# BPMLabLineRX.net
KiCad netlist of a schematic drawn in EAGLE
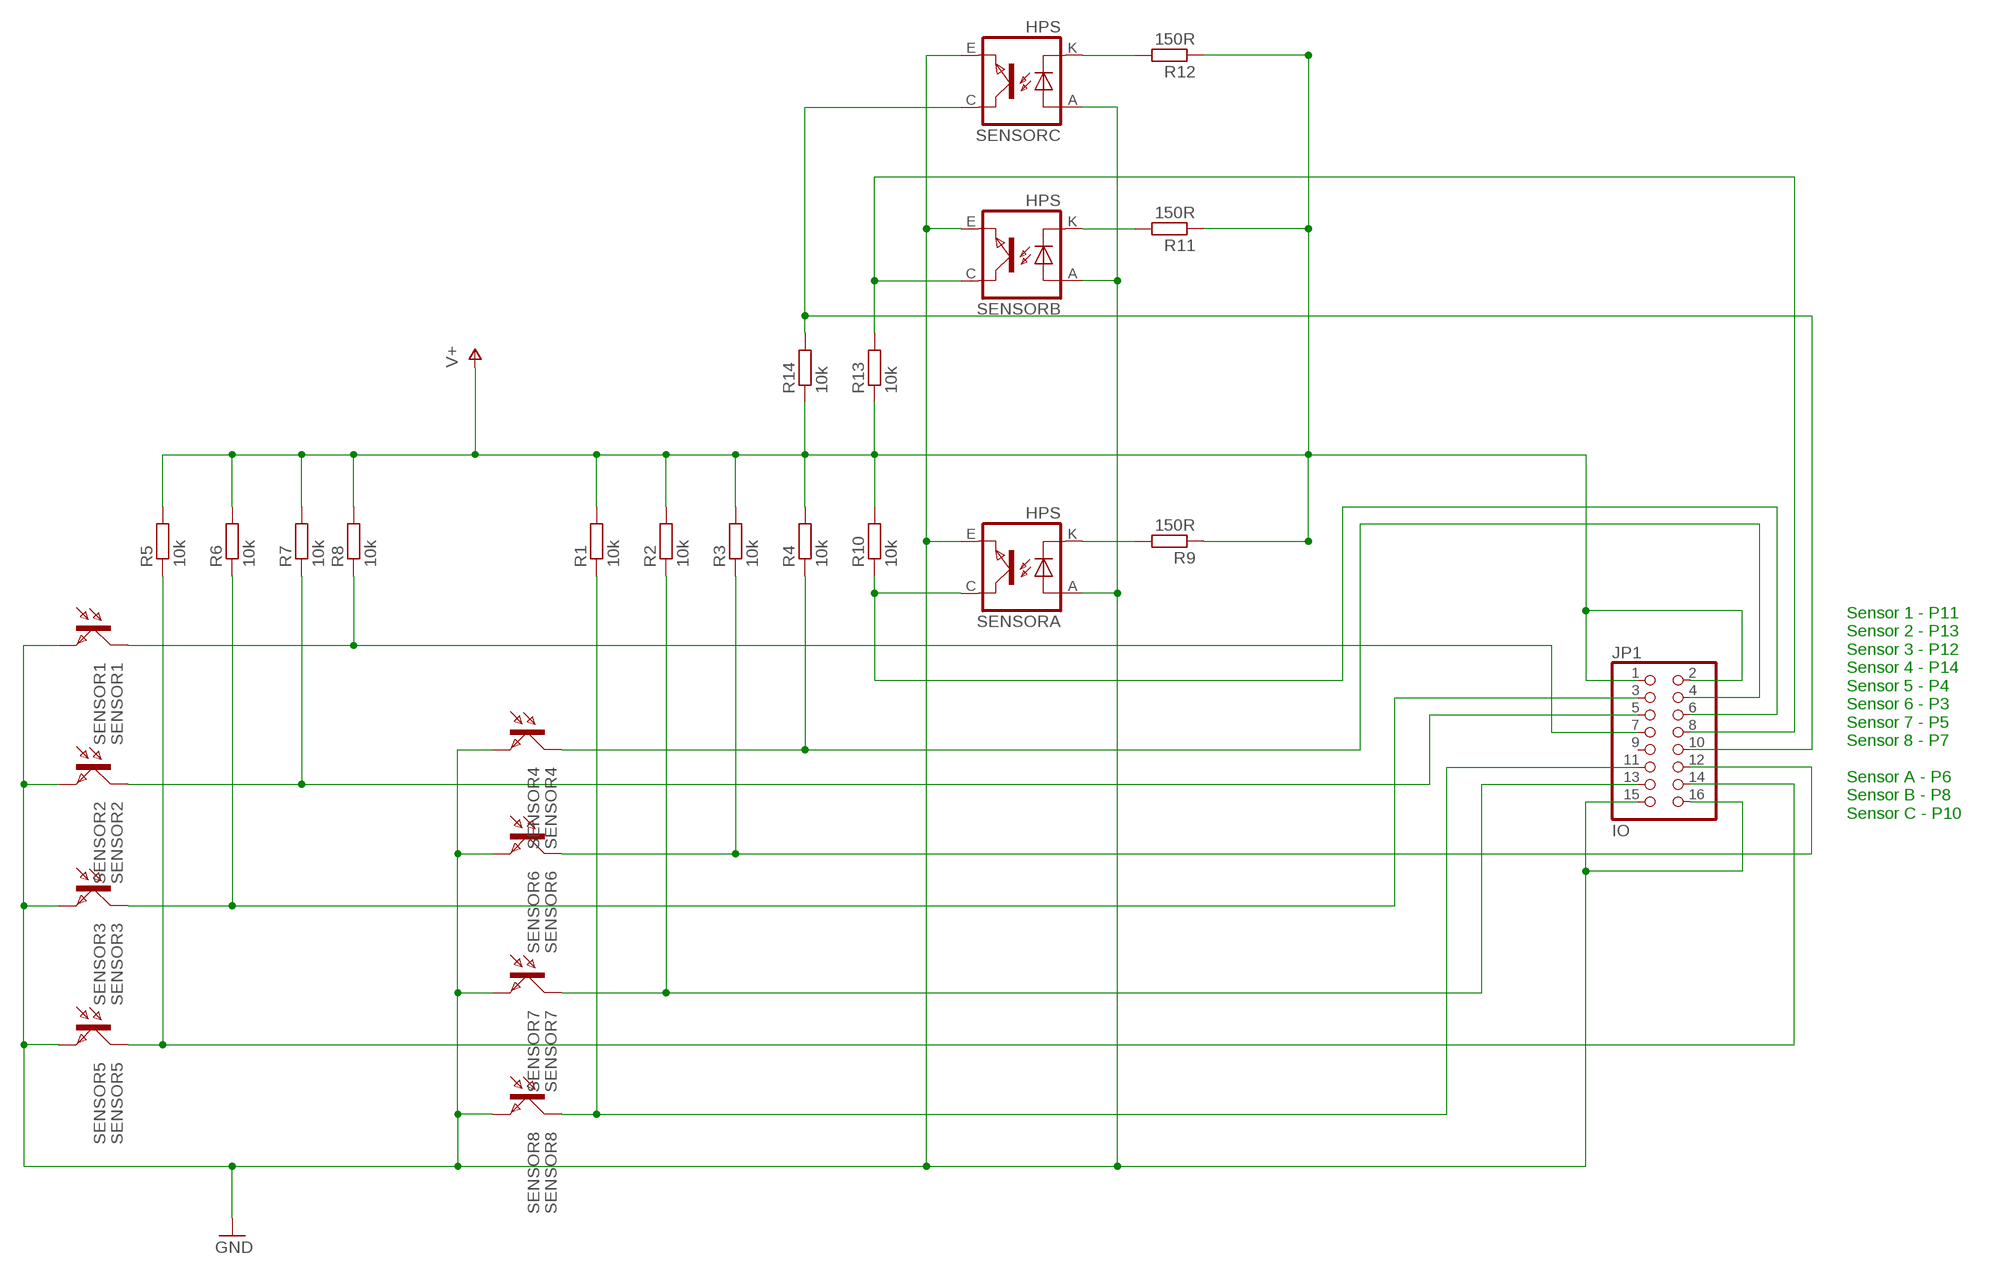
[diagram p0: schematic, sheet 1]

(export (version "E")
  (design (tool "Eeschema 10.0.6"))
  (components
    (comp (ref "JP1")
      (value "IO")
      (footprint "eagle-import:2X08")
      (libsource (lib "eagle-import") (part "PINHD-2X8"))
    )
    (comp (ref "R1")
      (value "10k")
      (footprint "eagle-import:M0805")
      (libsource (lib "eagle-import") (part "R-EU_M0805"))
    )
    (comp (ref "R2")
      (value "10k")
      (footprint "eagle-import:M0805")
      (libsource (lib "eagle-import") (part "R-EU_M0805"))
    )
    (comp (ref "R3")
      (value "10k")
      (footprint "eagle-import:M0805")
      (libsource (lib "eagle-import") (part "R-EU_M0805"))
    )
    (comp (ref "R4")
      (value "10k")
      (footprint "eagle-import:M0805")
      (libsource (lib "eagle-import") (part "R-EU_M0805"))
    )
    (comp (ref "R5")
      (value "10k")
      (footprint "eagle-import:M0805")
      (libsource (lib "eagle-import") (part "R-EU_M0805"))
    )
    (comp (ref "R6")
      (value "10k")
      (footprint "eagle-import:M0805")
      (libsource (lib "eagle-import") (part "R-EU_M0805"))
    )
    (comp (ref "R7")
      (value "10k")
      (footprint "eagle-import:M0805")
      (libsource (lib "eagle-import") (part "R-EU_M0805"))
    )
    (comp (ref "R8")
      (value "10k")
      (footprint "eagle-import:M0805")
      (libsource (lib "eagle-import") (part "R-EU_M0805"))
    )
    (comp (ref "R9")
      (value "150R")
      (footprint "eagle-import:M0805")
      (libsource (lib "eagle-import") (part "R-EU_M0805"))
    )
    (comp (ref "R10")
      (value "10k")
      (footprint "eagle-import:M0805")
      (libsource (lib "eagle-import") (part "R-EU_M0805"))
    )
    (comp (ref "R11")
      (value "150R")
      (footprint "eagle-import:M0805")
      (libsource (lib "eagle-import") (part "R-EU_M0805"))
    )
    (comp (ref "R12")
      (value "150R")
      (footprint "eagle-import:M0805")
      (libsource (lib "eagle-import") (part "R-EU_M0805"))
    )
    (comp (ref "R13")
      (value "10k")
      (footprint "eagle-import:M0805")
      (libsource (lib "eagle-import") (part "R-EU_M0805"))
    )
    (comp (ref "R14")
      (value "10k")
      (footprint "eagle-import:M0805")
      (libsource (lib "eagle-import") (part "R-EU_M0805"))
    )
    (comp (ref "SENSOR1")
      (value "SENSOR1")
      (footprint "eagle-import:BPX81")
      (libsource (lib "eagle-import") (part "BPX81"))
    )
    (comp (ref "SENSOR2")
      (value "SENSOR2")
      (footprint "eagle-import:BPX81")
      (libsource (lib "eagle-import") (part "BPX81"))
    )
    (comp (ref "SENSOR3")
      (value "SENSOR3")
      (footprint "eagle-import:BPX81")
      (libsource (lib "eagle-import") (part "BPX81"))
    )
    (comp (ref "SENSOR4")
      (value "SENSOR4")
      (footprint "eagle-import:BPX81")
      (libsource (lib "eagle-import") (part "BPX81"))
    )
    (comp (ref "SENSOR5")
      (value "SENSOR5")
      (footprint "eagle-import:BPX81")
      (libsource (lib "eagle-import") (part "BPX81"))
    )
    (comp (ref "SENSOR6")
      (value "SENSOR6")
      (footprint "eagle-import:BPX81")
      (libsource (lib "eagle-import") (part "BPX81"))
    )
    (comp (ref "SENSOR7")
      (value "SENSOR7")
      (footprint "eagle-import:BPX81")
      (libsource (lib "eagle-import") (part "BPX81"))
    )
    (comp (ref "SENSOR8")
      (value "SENSOR8")
      (footprint "eagle-import:BPX81")
      (libsource (lib "eagle-import") (part "BPX81"))
    )
    (comp (ref "SENSORA")
      (value "HPS")
      (footprint "eagle-import:TCRT5000")
      (libsource (lib "eagle-import") (part "TCRT5000"))
    )
    (comp (ref "SENSORB")
      (value "HPS")
      (footprint "eagle-import:TCRT5000")
      (libsource (lib "eagle-import") (part "TCRT5000"))
    )
    (comp (ref "SENSORC")
      (value "HPS")
      (footprint "eagle-import:TCRT5000")
      (libsource (lib "eagle-import") (part "TCRT5000"))
    )
  )
  (nets
    (net (code "1") (name "GND") (class "Default")
      (node (ref "JP1") (pin "15") (pinfunction "15_15") (pintype "passive"))
      (node (ref "JP1") (pin "16") (pinfunction "16_16") (pintype "passive"))
      (node (ref "SENSOR1") (pin "E") (pinfunction "E_E") (pintype "passive"))
      (node (ref "SENSOR2") (pin "E") (pinfunction "E_E") (pintype "passive"))
      (node (ref "SENSOR3") (pin "E") (pinfunction "E_E") (pintype "passive"))
      (node (ref "SENSOR4") (pin "E") (pinfunction "E_E") (pintype "passive"))
      (node (ref "SENSOR5") (pin "E") (pinfunction "E_E") (pintype "passive"))
      (node (ref "SENSOR6") (pin "E") (pinfunction "E_E") (pintype "passive"))
      (node (ref "SENSOR7") (pin "E") (pinfunction "E_E") (pintype "passive"))
      (node (ref "SENSOR8") (pin "E") (pinfunction "E_E") (pintype "passive"))
      (node (ref "SENSORA") (pin "A") (pinfunction "ANODE_A") (pintype "passive"))
      (node (ref "SENSORA") (pin "E") (pinfunction "EMITTER_E") (pintype "passive"))
      (node (ref "SENSORB") (pin "A") (pinfunction "ANODE_A") (pintype "passive"))
      (node (ref "SENSORB") (pin "E") (pinfunction "EMITTER_E") (pintype "passive"))
      (node (ref "SENSORC") (pin "A") (pinfunction "ANODE_A") (pintype "passive"))
      (node (ref "SENSORC") (pin "E") (pinfunction "EMITTER_E") (pintype "passive"))
    )
    (net (code "2") (name "Net-(JP1-Pad3)") (class "Default")
      (node (ref "JP1") (pin "3") (pinfunction "3_3") (pintype "passive"))
      (node (ref "R6") (pin "1") (pinfunction "1_1") (pintype "passive"))
      (node (ref "SENSOR3") (pin "C") (pinfunction "C_C") (pintype "passive"))
    )
    (net (code "3") (name "Net-(JP1-Pad4)") (class "Default")
      (node (ref "JP1") (pin "4") (pinfunction "4_4") (pintype "passive"))
      (node (ref "R4") (pin "1") (pinfunction "1_1") (pintype "passive"))
      (node (ref "SENSOR4") (pin "C") (pinfunction "C_C") (pintype "passive"))
    )
    (net (code "4") (name "Net-(JP1-Pad5)") (class "Default")
      (node (ref "JP1") (pin "5") (pinfunction "5_5") (pintype "passive"))
      (node (ref "R7") (pin "1") (pinfunction "1_1") (pintype "passive"))
      (node (ref "SENSOR2") (pin "C") (pinfunction "C_C") (pintype "passive"))
    )
    (net (code "5") (name "Net-(JP1-Pad7)") (class "Default")
      (node (ref "JP1") (pin "7") (pinfunction "7_7") (pintype "passive"))
      (node (ref "R8") (pin "1") (pinfunction "1_1") (pintype "passive"))
      (node (ref "SENSOR1") (pin "C") (pinfunction "C_C") (pintype "passive"))
    )
    (net (code "6") (name "Net-(JP1-Pad11)") (class "Default")
      (node (ref "JP1") (pin "11") (pinfunction "11_11") (pintype "passive"))
      (node (ref "R1") (pin "1") (pinfunction "1_1") (pintype "passive"))
      (node (ref "SENSOR8") (pin "C") (pinfunction "C_C") (pintype "passive"))
    )
    (net (code "7") (name "Net-(JP1-Pad12)") (class "Default")
      (node (ref "JP1") (pin "12") (pinfunction "12_12") (pintype "passive"))
      (node (ref "R3") (pin "1") (pinfunction "1_1") (pintype "passive"))
      (node (ref "SENSOR6") (pin "C") (pinfunction "C_C") (pintype "passive"))
    )
    (net (code "8") (name "Net-(JP1-Pad13)") (class "Default")
      (node (ref "JP1") (pin "13") (pinfunction "13_13") (pintype "passive"))
      (node (ref "R2") (pin "1") (pinfunction "1_1") (pintype "passive"))
      (node (ref "SENSOR7") (pin "C") (pinfunction "C_C") (pintype "passive"))
    )
    (net (code "9") (name "Net-(JP1-Pad14)") (class "Default")
      (node (ref "JP1") (pin "14") (pinfunction "14_14") (pintype "passive"))
      (node (ref "R5") (pin "1") (pinfunction "1_1") (pintype "passive"))
      (node (ref "SENSOR5") (pin "C") (pinfunction "C_C") (pintype "passive"))
    )
    (net (code "10") (name "Net-(SENSORA-CATHODE)") (class "Default")
      (node (ref "R9") (pin "2") (pinfunction "2_2") (pintype "passive"))
      (node (ref "SENSORA") (pin "K") (pinfunction "CATHODE_K") (pintype "passive"))
    )
    (net (code "11") (name "Net-(SENSORA-COLLECTOR)") (class "Default")
      (node (ref "JP1") (pin "6") (pinfunction "6_6") (pintype "passive"))
      (node (ref "R10") (pin "1") (pinfunction "1_1") (pintype "passive"))
      (node (ref "SENSORA") (pin "C") (pinfunction "COLLECTOR_C") (pintype "passive"))
    )
    (net (code "12") (name "Net-(SENSORB-CATHODE)") (class "Default")
      (node (ref "R11") (pin "2") (pinfunction "2_2") (pintype "passive"))
      (node (ref "SENSORB") (pin "K") (pinfunction "CATHODE_K") (pintype "passive"))
    )
    (net (code "13") (name "Net-(SENSORB-COLLECTOR)") (class "Default")
      (node (ref "JP1") (pin "8") (pinfunction "8_8") (pintype "passive"))
      (node (ref "R13") (pin "2") (pinfunction "2_2") (pintype "passive"))
      (node (ref "SENSORB") (pin "C") (pinfunction "COLLECTOR_C") (pintype "passive"))
    )
    (net (code "14") (name "Net-(SENSORC-CATHODE)") (class "Default")
      (node (ref "R12") (pin "2") (pinfunction "2_2") (pintype "passive"))
      (node (ref "SENSORC") (pin "K") (pinfunction "CATHODE_K") (pintype "passive"))
    )
    (net (code "15") (name "Net-(SENSORC-COLLECTOR)") (class "Default")
      (node (ref "JP1") (pin "10") (pinfunction "10_10") (pintype "passive"))
      (node (ref "R14") (pin "2") (pinfunction "2_2") (pintype "passive"))
      (node (ref "SENSORC") (pin "C") (pinfunction "COLLECTOR_C") (pintype "passive"))
    )
    (net (code "16") (name "V+") (class "Default")
      (node (ref "JP1") (pin "1") (pinfunction "1_1") (pintype "passive"))
      (node (ref "JP1") (pin "2") (pinfunction "2_2") (pintype "passive"))
      (node (ref "R1") (pin "2") (pinfunction "2_2") (pintype "passive"))
      (node (ref "R10") (pin "2") (pinfunction "2_2") (pintype "passive"))
      (node (ref "R11") (pin "1") (pinfunction "1_1") (pintype "passive"))
      (node (ref "R12") (pin "1") (pinfunction "1_1") (pintype "passive"))
      (node (ref "R13") (pin "1") (pinfunction "1_1") (pintype "passive"))
      (node (ref "R14") (pin "1") (pinfunction "1_1") (pintype "passive"))
      (node (ref "R2") (pin "2") (pinfunction "2_2") (pintype "passive"))
      (node (ref "R3") (pin "2") (pinfunction "2_2") (pintype "passive"))
      (node (ref "R4") (pin "2") (pinfunction "2_2") (pintype "passive"))
      (node (ref "R5") (pin "2") (pinfunction "2_2") (pintype "passive"))
      (node (ref "R6") (pin "2") (pinfunction "2_2") (pintype "passive"))
      (node (ref "R7") (pin "2") (pinfunction "2_2") (pintype "passive"))
      (node (ref "R8") (pin "2") (pinfunction "2_2") (pintype "passive"))
      (node (ref "R9") (pin "1") (pinfunction "1_1") (pintype "passive"))
    )
    (net (code "17") (name "unconnected-(JP1-Pad9)") (class "Default")
      (node (ref "JP1") (pin "9") (pinfunction "9_9") (pintype "passive"))
    )
  )
)
